# MD2017_Drive.net
KiCad netlist of a schematic drawn in EAGLE
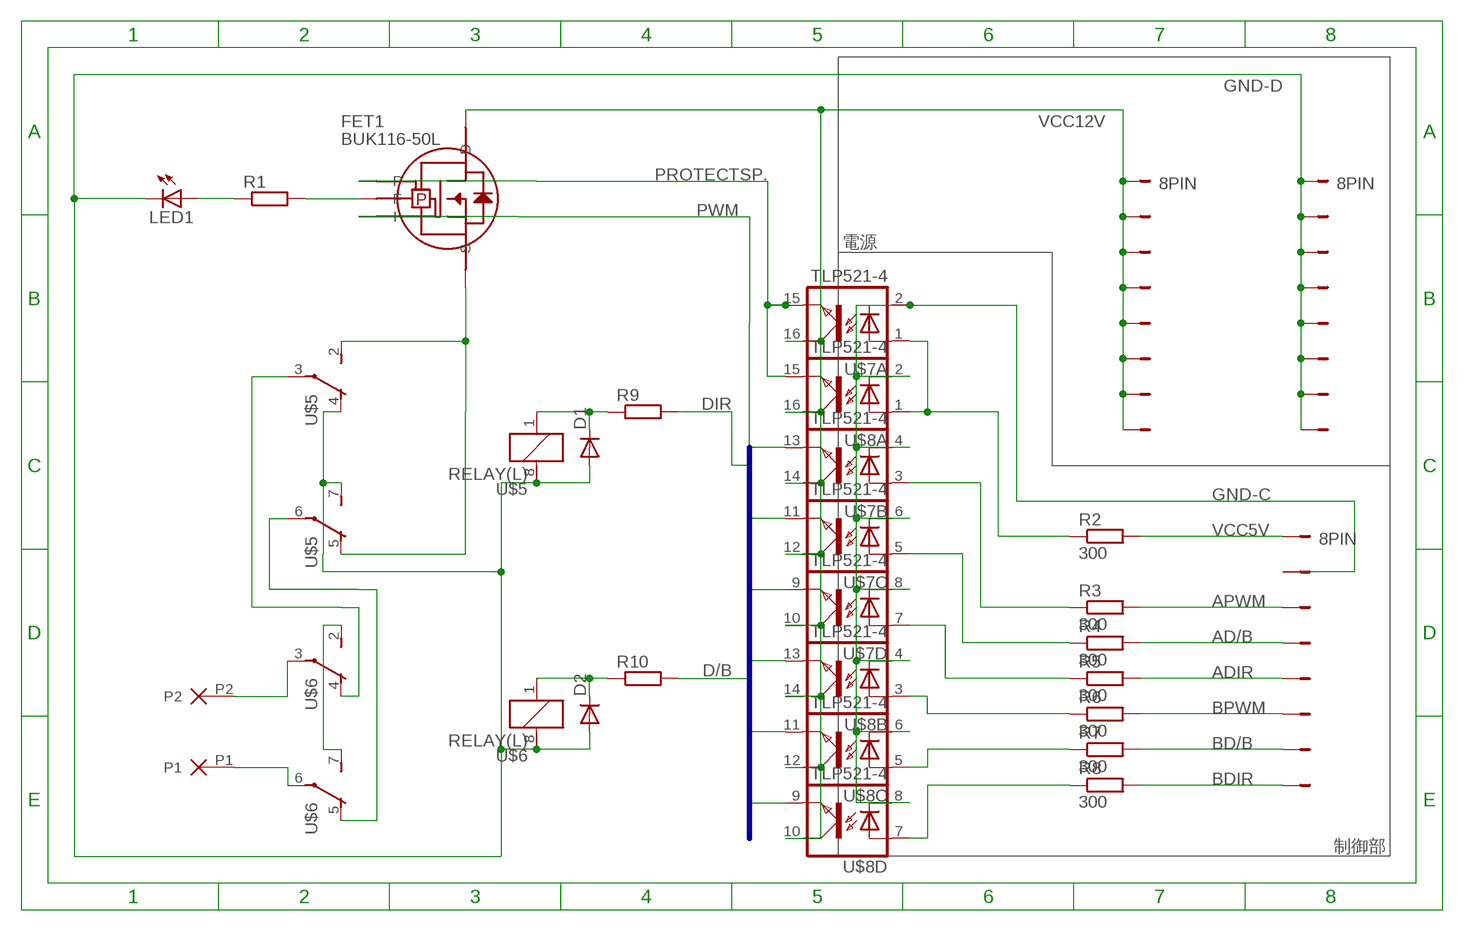
[diagram p0: schematic, sheet 1]

(export (version "E")
  (design (tool "Eeschema 10.0.6"))
  (components
    (comp (ref "D1")
      (value "DIODE7.5")
      (footprint "eagle-import:DIODE7.5")
      (libsource (lib "eagle-import") (part "DIODE7.5"))
    )
    (comp (ref "D2")
      (value "DIODE7.5")
      (footprint "eagle-import:DIODE7.5")
      (libsource (lib "eagle-import") (part "DIODE7.5"))
    )
    (comp (ref "FET1")
      (value "BUK116-50L")
      (footprint "eagle-import:BUK116-50L")
      (libsource (lib "eagle-import") (part "BUK116-50L"))
    )
    (comp (ref "LED1")
      (value "LED5MM")
      (footprint "eagle-import:LED5MM")
      (libsource (lib "eagle-import") (part "LED5MM"))
    )
    (comp (ref "POWERNPORT")
      (value "8PIN")
      (footprint "eagle-import:FH105-1X8SG")
      (libsource (lib "eagle-import") (part "8PIN"))
    )
    (comp (ref "POWERPPORT")
      (value "8PIN")
      (footprint "eagle-import:FH105-1X8SG")
      (libsource (lib "eagle-import") (part "8PIN"))
    )
    (comp (ref "R1")
      (value "R-EU_R3216W")
      (footprint "eagle-import:R3216W")
      (libsource (lib "eagle-import") (part "R-EU_R3216W"))
    )
    (comp (ref "R2")
      (value "300")
      (footprint "eagle-import:R3216W")
      (libsource (lib "eagle-import") (part "R-EU_R3216W"))
    )
    (comp (ref "R3")
      (value "300")
      (footprint "eagle-import:R3216W")
      (libsource (lib "eagle-import") (part "R-EU_R3216W"))
    )
    (comp (ref "R4")
      (value "300")
      (footprint "eagle-import:R3216W")
      (libsource (lib "eagle-import") (part "R-EU_R3216W"))
    )
    (comp (ref "R5")
      (value "300")
      (footprint "eagle-import:R3216W")
      (libsource (lib "eagle-import") (part "R-EU_R3216W"))
    )
    (comp (ref "R6")
      (value "300")
      (footprint "eagle-import:R3216W")
      (libsource (lib "eagle-import") (part "R-EU_R3216W"))
    )
    (comp (ref "R7")
      (value "300")
      (footprint "eagle-import:R3216W")
      (libsource (lib "eagle-import") (part "R-EU_R3216W"))
    )
    (comp (ref "R8")
      (value "300")
      (footprint "eagle-import:R3216W")
      (libsource (lib "eagle-import") (part "R-EU_R3216W"))
    )
    (comp (ref "R9")
      (value "R-EU_R3216W")
      (footprint "eagle-import:R3216W")
      (libsource (lib "eagle-import") (part "R-EU_R3216W"))
    )
    (comp (ref "R10")
      (value "R-EU_R3216W")
      (footprint "eagle-import:R3216W")
      (libsource (lib "eagle-import") (part "R-EU_R3216W"))
    )
    (comp (ref "SIGNALPORT")
      (value "8PIN")
      (footprint "eagle-import:FH105-1X8SG")
      (libsource (lib "eagle-import") (part "8PIN"))
    )
    (comp (ref "U$5")
      (value "RELAY(L)")
      (footprint "eagle-import:G2R2")
      (libsource (lib "eagle-import") (part "RELAY(L)"))
    )
    (comp (ref "U$6")
      (value "RELAY(L)")
      (footprint "eagle-import:G2R2")
      (libsource (lib "eagle-import") (part "RELAY(L)"))
    )
    (comp (ref "U$7")
      (value "TLP521-4")
      (footprint "eagle-import:16PIN")
      (libsource (lib "eagle-import") (part "TLP521-4"))
    )
    (comp (ref "U$8")
      (value "TLP521-4")
      (footprint "eagle-import:16PIN")
      (libsource (lib "eagle-import") (part "TLP521-4"))
    )
    (comp (ref "U$9") (value "2P") (footprint "eagle-import:2P") (libsource (lib "eagle-import") (part "2P")))
  )
  (nets
    (net (code "1") (name "/ADIR") (class "Default")
      (node (ref "R5") (pin "2") (pinfunction "2_2") (pintype "passive"))
      (node (ref "SIGNALPORT") (pin "5") (pinfunction "P$1_5") (pintype "passive"))
    )
    (net (code "2") (name "/AD{slash}B") (class "Default")
      (node (ref "R4") (pin "2") (pinfunction "2_2") (pintype "passive"))
      (node (ref "SIGNALPORT") (pin "4") (pinfunction "P$1_4") (pintype "passive"))
    )
    (net (code "3") (name "/APWM") (class "Default")
      (node (ref "R3") (pin "2") (pinfunction "2_2") (pintype "passive"))
      (node (ref "SIGNALPORT") (pin "3") (pinfunction "P$1_3") (pintype "passive"))
    )
    (net (code "4") (name "/BDIR") (class "Default")
      (node (ref "R8") (pin "2") (pinfunction "2_2") (pintype "passive"))
      (node (ref "SIGNALPORT") (pin "8") (pinfunction "P$1_8") (pintype "passive"))
    )
    (net (code "5") (name "/BD{slash}B") (class "Default")
      (node (ref "R7") (pin "2") (pinfunction "2_2") (pintype "passive"))
      (node (ref "SIGNALPORT") (pin "7") (pinfunction "P$1_7") (pintype "passive"))
    )
    (net (code "6") (name "/BPWM") (class "Default")
      (node (ref "R6") (pin "2") (pinfunction "2_2") (pintype "passive"))
      (node (ref "SIGNALPORT") (pin "6") (pinfunction "P$1_6") (pintype "passive"))
    )
    (net (code "7") (name "/DIR") (class "Default")
      (node (ref "R9") (pin "2") (pinfunction "2_2") (pintype "passive"))
      (node (ref "U$7") (pin "9") (pinfunction "EMIT_9") (pintype "passive"))
      (node (ref "U$8") (pin "9") (pinfunction "EMIT_9") (pintype "passive"))
    )
    (net (code "8") (name "/D{slash}B") (class "Default")
      (node (ref "R10") (pin "2") (pinfunction "2_2") (pintype "passive"))
      (node (ref "U$7") (pin "11") (pinfunction "EMIT_11") (pintype "passive"))
      (node (ref "U$8") (pin "11") (pinfunction "EMIT_11") (pintype "passive"))
    )
    (net (code "9") (name "/GND-C") (class "Default")
      (node (ref "SIGNALPORT") (pin "2") (pinfunction "P$1_2") (pintype "passive"))
      (node (ref "U$7") (pin "2") (pinfunction "C_2") (pintype "passive"))
      (node (ref "U$7") (pin "4") (pinfunction "C_4") (pintype "passive"))
      (node (ref "U$7") (pin "6") (pinfunction "C_6") (pintype "passive"))
      (node (ref "U$7") (pin "8") (pinfunction "C_8") (pintype "passive"))
      (node (ref "U$8") (pin "2") (pinfunction "C_2") (pintype "passive"))
      (node (ref "U$8") (pin "4") (pinfunction "C_4") (pintype "passive"))
      (node (ref "U$8") (pin "6") (pinfunction "C_6") (pintype "passive"))
      (node (ref "U$8") (pin "8") (pinfunction "C_8") (pintype "passive"))
    )
    (net (code "10") (name "/GND-D") (class "Default")
      (node (ref "D1") (pin "PA") (pinfunction "A_PA") (pintype "passive"))
      (node (ref "D2") (pin "PA") (pinfunction "A_PA") (pintype "passive"))
      (node (ref "LED1") (pin "K") (pinfunction "C_K") (pintype "passive"))
      (node (ref "POWERNPORT") (pin "1") (pinfunction "P$1_1") (pintype "passive"))
      (node (ref "POWERNPORT") (pin "2") (pinfunction "P$1_2") (pintype "passive"))
      (node (ref "POWERNPORT") (pin "3") (pinfunction "P$1_3") (pintype "passive"))
      (node (ref "POWERNPORT") (pin "4") (pinfunction "P$1_4") (pintype "passive"))
      (node (ref "POWERNPORT") (pin "5") (pinfunction "P$1_5") (pintype "passive"))
      (node (ref "POWERNPORT") (pin "6") (pinfunction "P$1_6") (pintype "passive"))
      (node (ref "POWERNPORT") (pin "7") (pinfunction "P$1_7") (pintype "passive"))
      (node (ref "POWERNPORT") (pin "8") (pinfunction "P$1_8") (pintype "passive"))
      (node (ref "U$5") (pin "4") (pinfunction "O_4") (pintype "passive"))
      (node (ref "U$5") (pin "7") (pinfunction "S_7") (pintype "passive"))
      (node (ref "U$5") (pin "8") (pinfunction "2_8") (pintype "passive"))
      (node (ref "U$6") (pin "8") (pinfunction "2_8") (pintype "passive"))
    )
    (net (code "11") (name "/PROTECTSP.") (class "Default")
      (node (ref "FET1") (pin "4") (pinfunction "P_4") (pintype "passive"))
      (node (ref "U$7") (pin "15") (pinfunction "EMIT_15") (pintype "passive"))
      (node (ref "U$8") (pin "15") (pinfunction "EMIT_15") (pintype "passive"))
    )
    (net (code "12") (name "/PWM") (class "Default")
      (node (ref "FET1") (pin "1") (pinfunction "I_1") (pintype "passive"))
      (node (ref "U$7") (pin "13") (pinfunction "EMIT_13") (pintype "passive"))
      (node (ref "U$8") (pin "13") (pinfunction "EMIT_13") (pintype "passive"))
    )
    (net (code "13") (name "/VCC5V") (class "Default")
      (node (ref "R2") (pin "2") (pinfunction "2_2") (pintype "passive"))
      (node (ref "SIGNALPORT") (pin "1") (pinfunction "P$1_1") (pintype "passive"))
    )
    (net (code "14") (name "/VCC12V") (class "Default")
      (node (ref "FET1") (pin "3") (pinfunction "D_3") (pintype "passive"))
      (node (ref "POWERPPORT") (pin "1") (pinfunction "P$1_1") (pintype "passive"))
      (node (ref "POWERPPORT") (pin "2") (pinfunction "P$1_2") (pintype "passive"))
      (node (ref "POWERPPORT") (pin "3") (pinfunction "P$1_3") (pintype "passive"))
      (node (ref "POWERPPORT") (pin "4") (pinfunction "P$1_4") (pintype "passive"))
      (node (ref "POWERPPORT") (pin "5") (pinfunction "P$1_5") (pintype "passive"))
      (node (ref "POWERPPORT") (pin "6") (pinfunction "P$1_6") (pintype "passive"))
      (node (ref "POWERPPORT") (pin "7") (pinfunction "P$1_7") (pintype "passive"))
      (node (ref "POWERPPORT") (pin "8") (pinfunction "P$1_8") (pintype "passive"))
      (node (ref "U$7") (pin "10") (pinfunction "COL_10") (pintype "passive"))
      (node (ref "U$7") (pin "12") (pinfunction "COL_12") (pintype "passive"))
      (node (ref "U$7") (pin "14") (pinfunction "COL_14") (pintype "passive"))
      (node (ref "U$7") (pin "16") (pinfunction "COL_16") (pintype "passive"))
      (node (ref "U$8") (pin "10") (pinfunction "COL_10") (pintype "passive"))
      (node (ref "U$8") (pin "12") (pinfunction "COL_12") (pintype "passive"))
      (node (ref "U$8") (pin "14") (pinfunction "COL_14") (pintype "passive"))
      (node (ref "U$8") (pin "16") (pinfunction "COL_16") (pintype "passive"))
    )
    (net (code "15") (name "Net-(D1-C)") (class "Default")
      (node (ref "D1") (pin "PK") (pinfunction "C_PK") (pintype "passive"))
      (node (ref "R9") (pin "1") (pinfunction "1_1") (pintype "passive"))
      (node (ref "U$5") (pin "1") (pinfunction "1_1") (pintype "passive"))
    )
    (net (code "16") (name "Net-(D2-C)") (class "Default")
      (node (ref "D2") (pin "PK") (pinfunction "C_PK") (pintype "passive"))
      (node (ref "R10") (pin "1") (pinfunction "1_1") (pintype "passive"))
      (node (ref "U$6") (pin "1") (pinfunction "1_1") (pintype "passive"))
    )
    (net (code "17") (name "Net-(FET1-F)") (class "Default")
      (node (ref "FET1") (pin "2") (pinfunction "F_2") (pintype "passive"))
      (node (ref "R1") (pin "2") (pinfunction "2_2") (pintype "passive"))
    )
    (net (code "18") (name "Net-(FET1-S)") (class "Default")
      (node (ref "FET1") (pin "5") (pinfunction "S_5") (pintype "passive"))
      (node (ref "U$5") (pin "2") (pinfunction "S_2") (pintype "passive"))
      (node (ref "U$5") (pin "5") (pinfunction "O_5") (pintype "passive"))
    )
    (net (code "19") (name "Net-(LED1-PadA)") (class "Default")
      (node (ref "LED1") (pin "A") (pinfunction "A_A") (pintype "passive"))
      (node (ref "R1") (pin "1") (pinfunction "1_1") (pintype "passive"))
    )
    (net (code "20") (name "Net-(U$5B-P)") (class "Default")
      (node (ref "U$5") (pin "6") (pinfunction "P_6") (pintype "passive"))
      (node (ref "U$6") (pin "5") (pinfunction "O_5") (pintype "passive"))
    )
    (net (code "21") (name "Net-(U$5C-P)") (class "Default")
      (node (ref "U$5") (pin "3") (pinfunction "P_3") (pintype "passive"))
      (node (ref "U$6") (pin "4") (pinfunction "O_4") (pintype "passive"))
    )
    (net (code "22") (name "Net-(U$6B-P)") (class "Default")
      (node (ref "U$6") (pin "6") (pinfunction "P_6") (pintype "passive"))
      (node (ref "U$9") (pin "P1") (pinfunction "P1_P1") (pintype "bidirectional"))
    )
    (net (code "23") (name "Net-(U$6B-S)") (class "Default")
      (node (ref "U$6") (pin "2") (pinfunction "S_2") (pintype "passive"))
      (node (ref "U$6") (pin "7") (pinfunction "S_7") (pintype "passive"))
    )
    (net (code "24") (name "Net-(U$6C-P)") (class "Default")
      (node (ref "U$6") (pin "3") (pinfunction "P_3") (pintype "passive"))
      (node (ref "U$9") (pin "P2") (pinfunction "P2_P2") (pintype "bidirectional"))
    )
    (net (code "25") (name "Net-(U$7A-A)") (class "Default")
      (node (ref "R2") (pin "1") (pinfunction "1_1") (pintype "passive"))
      (node (ref "U$7") (pin "1") (pinfunction "A_1") (pintype "passive"))
      (node (ref "U$8") (pin "1") (pinfunction "A_1") (pintype "passive"))
    )
    (net (code "26") (name "Net-(U$7B-A)") (class "Default")
      (node (ref "R3") (pin "1") (pinfunction "1_1") (pintype "passive"))
      (node (ref "U$7") (pin "3") (pinfunction "A_3") (pintype "passive"))
    )
    (net (code "27") (name "Net-(U$7C-A)") (class "Default")
      (node (ref "R4") (pin "1") (pinfunction "1_1") (pintype "passive"))
      (node (ref "U$7") (pin "5") (pinfunction "A_5") (pintype "passive"))
    )
    (net (code "28") (name "Net-(U$7D-A)") (class "Default")
      (node (ref "R5") (pin "1") (pinfunction "1_1") (pintype "passive"))
      (node (ref "U$7") (pin "7") (pinfunction "A_7") (pintype "passive"))
    )
    (net (code "29") (name "Net-(U$8B-A)") (class "Default")
      (node (ref "R6") (pin "1") (pinfunction "1_1") (pintype "passive"))
      (node (ref "U$8") (pin "3") (pinfunction "A_3") (pintype "passive"))
    )
    (net (code "30") (name "Net-(U$8C-A)") (class "Default")
      (node (ref "R7") (pin "1") (pinfunction "1_1") (pintype "passive"))
      (node (ref "U$8") (pin "5") (pinfunction "A_5") (pintype "passive"))
    )
    (net (code "31") (name "Net-(U$8D-A)") (class "Default")
      (node (ref "R8") (pin "1") (pinfunction "1_1") (pintype "passive"))
      (node (ref "U$8") (pin "7") (pinfunction "A_7") (pintype "passive"))
    )
  )
)
